# Top_Level.net
KiCad netlist of a schematic drawn in Altium Designer
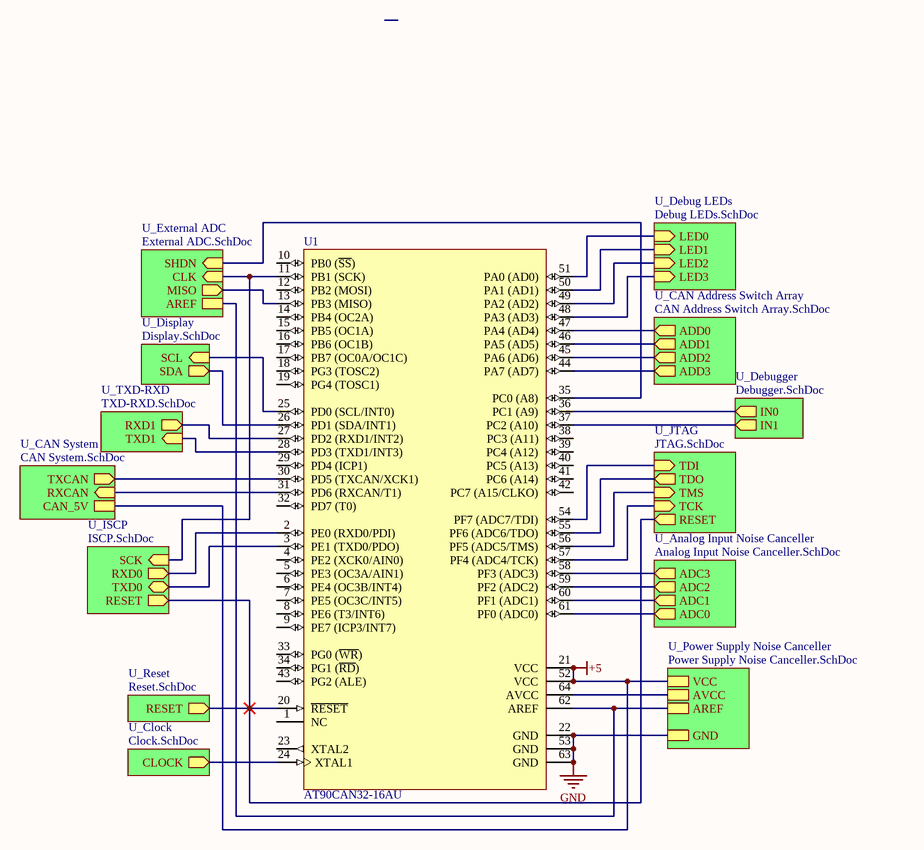
[diagram p0: Top Level.SchDoc]

(export (version "E")
  (design (tool "Eeschema 10.0.6"))
  (components
    (comp (ref "U1")
      (value "AT90CAN32-16AU")
      (footprint "64A_N")
      (libsource (lib "Altium Content Vault") (part "MC-8B-AT90CAN32-SQ64"))
    )
  )
  (nets
    (net (code "1") (name "+5") (class "Default")
      (node (ref "U1") (pin "21") (pinfunction "VCC_21") (pintype "power_in"))
      (node (ref "U1") (pin "52") (pinfunction "VCC_52") (pintype "power_in"))
    )
    (net (code "2") (name "/ADC0") (class "Default")
      (node (ref "U1") (pin "61") (pinfunction "PF0_(ADC0)_61") (pintype "bidirectional"))
    )
    (net (code "3") (name "/ADC1") (class "Default")
      (node (ref "U1") (pin "60") (pinfunction "PF1_(ADC1)_60") (pintype "bidirectional"))
    )
    (net (code "4") (name "/ADC2") (class "Default")
      (node (ref "U1") (pin "59") (pinfunction "PF2_(ADC2)_59") (pintype "bidirectional"))
    )
    (net (code "5") (name "/ADC3") (class "Default")
      (node (ref "U1") (pin "58") (pinfunction "PF3_(ADC3)_58") (pintype "bidirectional"))
    )
    (net (code "6") (name "/ADD0") (class "Default")
      (node (ref "U1") (pin "47") (pinfunction "PA4_(AD4)_47") (pintype "bidirectional"))
    )
    (net (code "7") (name "/ADD1") (class "Default")
      (node (ref "U1") (pin "46") (pinfunction "PA5_(AD5)_46") (pintype "bidirectional"))
    )
    (net (code "8") (name "/ADD2") (class "Default")
      (node (ref "U1") (pin "45") (pinfunction "PA6_(AD6)_45") (pintype "bidirectional"))
    )
    (net (code "9") (name "/ADD3") (class "Default")
      (node (ref "U1") (pin "44") (pinfunction "PA7_(AD7)_44") (pintype "bidirectional"))
    )
    (net (code "10") (name "/AREF") (class "Default")
      (node (ref "U1") (pin "62") (pinfunction "AREF_62") (pintype "power_in"))
    )
    (net (code "11") (name "/AVCC") (class "Default")
      (node (ref "U1") (pin "64") (pinfunction "AVCC_64") (pintype "power_in"))
    )
    (net (code "12") (name "/CLK") (class "Default")
      (node (ref "U1") (pin "11") (pinfunction "PB1_(SCK)_11") (pintype "bidirectional"))
    )
    (net (code "13") (name "/CLOCK") (class "Default")
      (node (ref "U1") (pin "24") (pinfunction "XTAL1_24") (pintype "input"))
    )
    (net (code "14") (name "/IN0") (class "Default")
      (node (ref "U1") (pin "36") (pinfunction "PC1_(A9)_36") (pintype "bidirectional"))
    )
    (net (code "15") (name "/IN1") (class "Default")
      (node (ref "U1") (pin "37") (pinfunction "PC2_(A10)_37") (pintype "bidirectional"))
    )
    (net (code "16") (name "/LED0") (class "Default")
      (node (ref "U1") (pin "51") (pinfunction "PA0_(AD0)_51") (pintype "bidirectional"))
    )
    (net (code "17") (name "/LED1") (class "Default")
      (node (ref "U1") (pin "50") (pinfunction "PA1_(AD1)_50") (pintype "bidirectional"))
    )
    (net (code "18") (name "/LED2") (class "Default")
      (node (ref "U1") (pin "49") (pinfunction "PA2_(AD2)_49") (pintype "bidirectional"))
    )
    (net (code "19") (name "/LED3") (class "Default")
      (node (ref "U1") (pin "48") (pinfunction "PA3_(AD3)_48") (pintype "bidirectional"))
    )
    (net (code "20") (name "/MISO") (class "Default")
      (node (ref "U1") (pin "13") (pinfunction "PB3_(MISO)_13") (pintype "bidirectional"))
    )
    (net (code "21") (name "/RESET") (class "Default")
      (node (ref "U1") (pin "20") (pinfunction "~{RESET}_20") (pintype "input+no_connect"))
    )
    (net (code "22") (name "/RXCAN") (class "Default")
      (node (ref "U1") (pin "31") (pinfunction "PD6_(RXCAN/T1)_31") (pintype "bidirectional"))
    )
    (net (code "23") (name "/RXD0") (class "Default")
      (node (ref "U1") (pin "2") (pinfunction "PE0_(RXD0/PDI)_2") (pintype "bidirectional"))
    )
    (net (code "24") (name "/RXD1") (class "Default")
      (node (ref "U1") (pin "27") (pinfunction "PD2_(RXD1/INT2)_27") (pintype "bidirectional"))
    )
    (net (code "25") (name "/SCL") (class "Default")
      (node (ref "U1") (pin "25") (pinfunction "PD0_(SCL/INT0)_25") (pintype "bidirectional"))
    )
    (net (code "26") (name "/SDA") (class "Default")
      (node (ref "U1") (pin "26") (pinfunction "PD1_(SDA/INT1)_26") (pintype "bidirectional"))
    )
    (net (code "27") (name "/SHDN") (class "Default")
      (node (ref "U1") (pin "35") (pinfunction "PC0_(A8)_35") (pintype "bidirectional"))
    )
    (net (code "28") (name "/TCK") (class "Default")
      (node (ref "U1") (pin "57") (pinfunction "PF4_(ADC4/TCK)_57") (pintype "bidirectional"))
    )
    (net (code "29") (name "/TDI") (class "Default")
      (node (ref "U1") (pin "54") (pinfunction "PF7_(ADC7/TDI)_54") (pintype "bidirectional"))
    )
    (net (code "30") (name "/TDO") (class "Default")
      (node (ref "U1") (pin "55") (pinfunction "PF6_(ADC6/TDO)_55") (pintype "bidirectional"))
    )
    (net (code "31") (name "/TMS") (class "Default")
      (node (ref "U1") (pin "56") (pinfunction "PF5_(ADC5/TMS)_56") (pintype "bidirectional"))
    )
    (net (code "32") (name "/TXCAN") (class "Default")
      (node (ref "U1") (pin "30") (pinfunction "PD5_(TXCAN/XCK1)_30") (pintype "bidirectional"))
    )
    (net (code "33") (name "/TXD0") (class "Default")
      (node (ref "U1") (pin "3") (pinfunction "PE1_(TXD0/PDO)_3") (pintype "bidirectional"))
    )
    (net (code "34") (name "/TXD1") (class "Default")
      (node (ref "U1") (pin "28") (pinfunction "PD3_(TXD1/INT3)_28") (pintype "bidirectional"))
    )
    (net (code "35") (name "GND") (class "Default")
      (node (ref "U1") (pin "22") (pinfunction "GND_22") (pintype "power_in"))
      (node (ref "U1") (pin "53") (pinfunction "GND_53") (pintype "power_in"))
      (node (ref "U1") (pin "63") (pinfunction "GND_63") (pintype "power_in"))
    )
    (net (code "36") (name "unconnected-(U1-NC-Pad1)") (class "Default")
      (node (ref "U1") (pin "1") (pinfunction "NC_1") (pintype "passive"))
    )
    (net (code "37") (name "unconnected-(U1-PB0_(~{SS})-Pad10)") (class "Default")
      (node (ref "U1") (pin "10") (pinfunction "PB0_(~{SS})_10") (pintype "bidirectional"))
    )
    (net (code "38") (name "unconnected-(U1-PB2_(MOSI)-Pad12)") (class "Default")
      (node (ref "U1") (pin "12") (pinfunction "PB2_(MOSI)_12") (pintype "bidirectional"))
    )
    (net (code "39") (name "unconnected-(U1-PB4_(OC2A)-Pad14)") (class "Default")
      (node (ref "U1") (pin "14") (pinfunction "PB4_(OC2A)_14") (pintype "bidirectional"))
    )
    (net (code "40") (name "unconnected-(U1-PB5_(OC1A)-Pad15)") (class "Default")
      (node (ref "U1") (pin "15") (pinfunction "PB5_(OC1A)_15") (pintype "bidirectional"))
    )
    (net (code "41") (name "unconnected-(U1-PB6_(OC1B)-Pad16)") (class "Default")
      (node (ref "U1") (pin "16") (pinfunction "PB6_(OC1B)_16") (pintype "bidirectional"))
    )
    (net (code "42") (name "unconnected-(U1-PB7_(OC0A{slash}OC1C)-Pad17)") (class "Default")
      (node (ref "U1") (pin "17") (pinfunction "PB7_(OC0A/OC1C)_17") (pintype "bidirectional"))
    )
    (net (code "43") (name "unconnected-(U1-PC3_(A11)-Pad38)") (class "Default")
      (node (ref "U1") (pin "38") (pinfunction "PC3_(A11)_38") (pintype "bidirectional"))
    )
    (net (code "44") (name "unconnected-(U1-PC4_(A12)-Pad39)") (class "Default")
      (node (ref "U1") (pin "39") (pinfunction "PC4_(A12)_39") (pintype "bidirectional"))
    )
    (net (code "45") (name "unconnected-(U1-PC5_(A13)-Pad40)") (class "Default")
      (node (ref "U1") (pin "40") (pinfunction "PC5_(A13)_40") (pintype "bidirectional"))
    )
    (net (code "46") (name "unconnected-(U1-PC6_(A14)-Pad41)") (class "Default")
      (node (ref "U1") (pin "41") (pinfunction "PC6_(A14)_41") (pintype "bidirectional"))
    )
    (net (code "47") (name "unconnected-(U1-PC7_(A15{slash}CLKO)-Pad42)") (class "Default")
      (node (ref "U1") (pin "42") (pinfunction "PC7_(A15/CLKO)_42") (pintype "bidirectional"))
    )
    (net (code "48") (name "unconnected-(U1-PD4_(ICP1)-Pad29)") (class "Default")
      (node (ref "U1") (pin "29") (pinfunction "PD4_(ICP1)_29") (pintype "bidirectional"))
    )
    (net (code "49") (name "unconnected-(U1-PD7_(T0)-Pad32)") (class "Default")
      (node (ref "U1") (pin "32") (pinfunction "PD7_(T0)_32") (pintype "bidirectional"))
    )
    (net (code "50") (name "unconnected-(U1-PE2_(XCK0{slash}AIN0)-Pad4)") (class "Default")
      (node (ref "U1") (pin "4") (pinfunction "PE2_(XCK0/AIN0)_4") (pintype "bidirectional"))
    )
    (net (code "51") (name "unconnected-(U1-PE3_(OC3A{slash}AIN1)-Pad5)") (class "Default")
      (node (ref "U1") (pin "5") (pinfunction "PE3_(OC3A/AIN1)_5") (pintype "bidirectional"))
    )
    (net (code "52") (name "unconnected-(U1-PE4_(OC3B{slash}INT4)-Pad6)") (class "Default")
      (node (ref "U1") (pin "6") (pinfunction "PE4_(OC3B/INT4)_6") (pintype "bidirectional"))
    )
    (net (code "53") (name "unconnected-(U1-PE5_(OC3C{slash}INT5)-Pad7)") (class "Default")
      (node (ref "U1") (pin "7") (pinfunction "PE5_(OC3C/INT5)_7") (pintype "bidirectional"))
    )
    (net (code "54") (name "unconnected-(U1-PE6_(T3{slash}INT6)-Pad8)") (class "Default")
      (node (ref "U1") (pin "8") (pinfunction "PE6_(T3/INT6)_8") (pintype "bidirectional"))
    )
    (net (code "55") (name "unconnected-(U1-PE7_(ICP3{slash}INT7)-Pad9)") (class "Default")
      (node (ref "U1") (pin "9") (pinfunction "PE7_(ICP3/INT7)_9") (pintype "bidirectional"))
    )
    (net (code "56") (name "unconnected-(U1-PG0_(~{WR})-Pad33)") (class "Default")
      (node (ref "U1") (pin "33") (pinfunction "PG0_(~{WR})_33") (pintype "bidirectional"))
    )
    (net (code "57") (name "unconnected-(U1-PG1_(~{RD})-Pad34)") (class "Default")
      (node (ref "U1") (pin "34") (pinfunction "PG1_(~{RD})_34") (pintype "bidirectional"))
    )
    (net (code "58") (name "unconnected-(U1-PG2_(ALE)-Pad43)") (class "Default")
      (node (ref "U1") (pin "43") (pinfunction "PG2_(ALE)_43") (pintype "bidirectional"))
    )
    (net (code "59") (name "unconnected-(U1-PG3_(TOSC2)-Pad18)") (class "Default")
      (node (ref "U1") (pin "18") (pinfunction "PG3_(TOSC2)_18") (pintype "bidirectional"))
    )
    (net (code "60") (name "unconnected-(U1-PG4_(TOSC1)-Pad19)") (class "Default")
      (node (ref "U1") (pin "19") (pinfunction "PG4_(TOSC1)_19") (pintype "bidirectional"))
    )
    (net (code "61") (name "unconnected-(U1-XTAL2-Pad23)") (class "Default")
      (node (ref "U1") (pin "23") (pinfunction "XTAL2_23") (pintype "output"))
    )
  )
)
